# STM32H745.net
KiCad netlist of a schematic drawn in Altium Designer
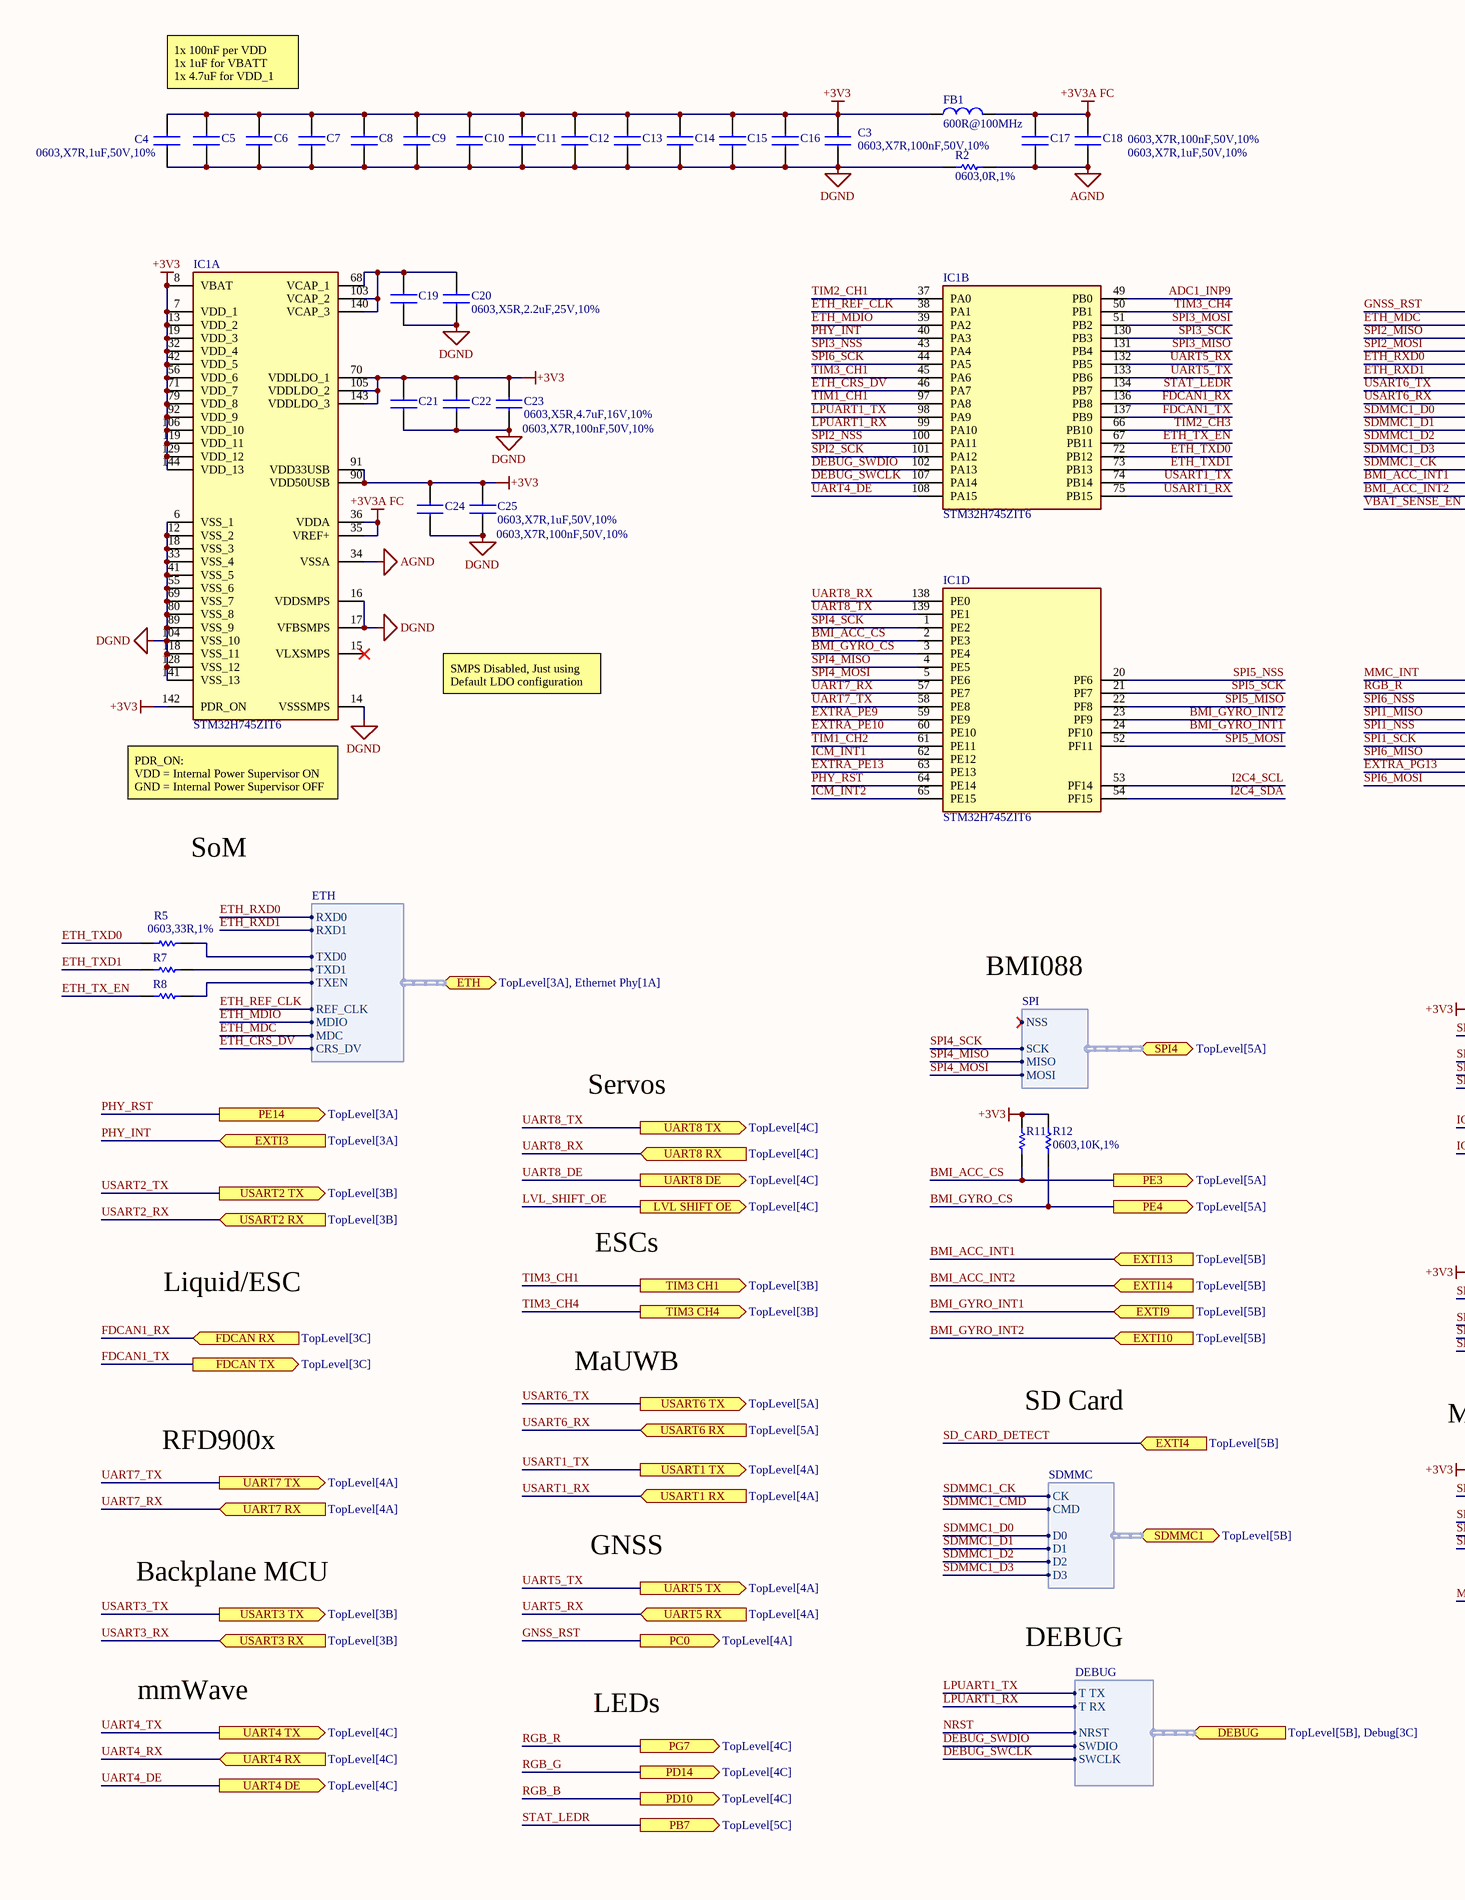
[diagram p0: STM32H745.SchDoc, left]
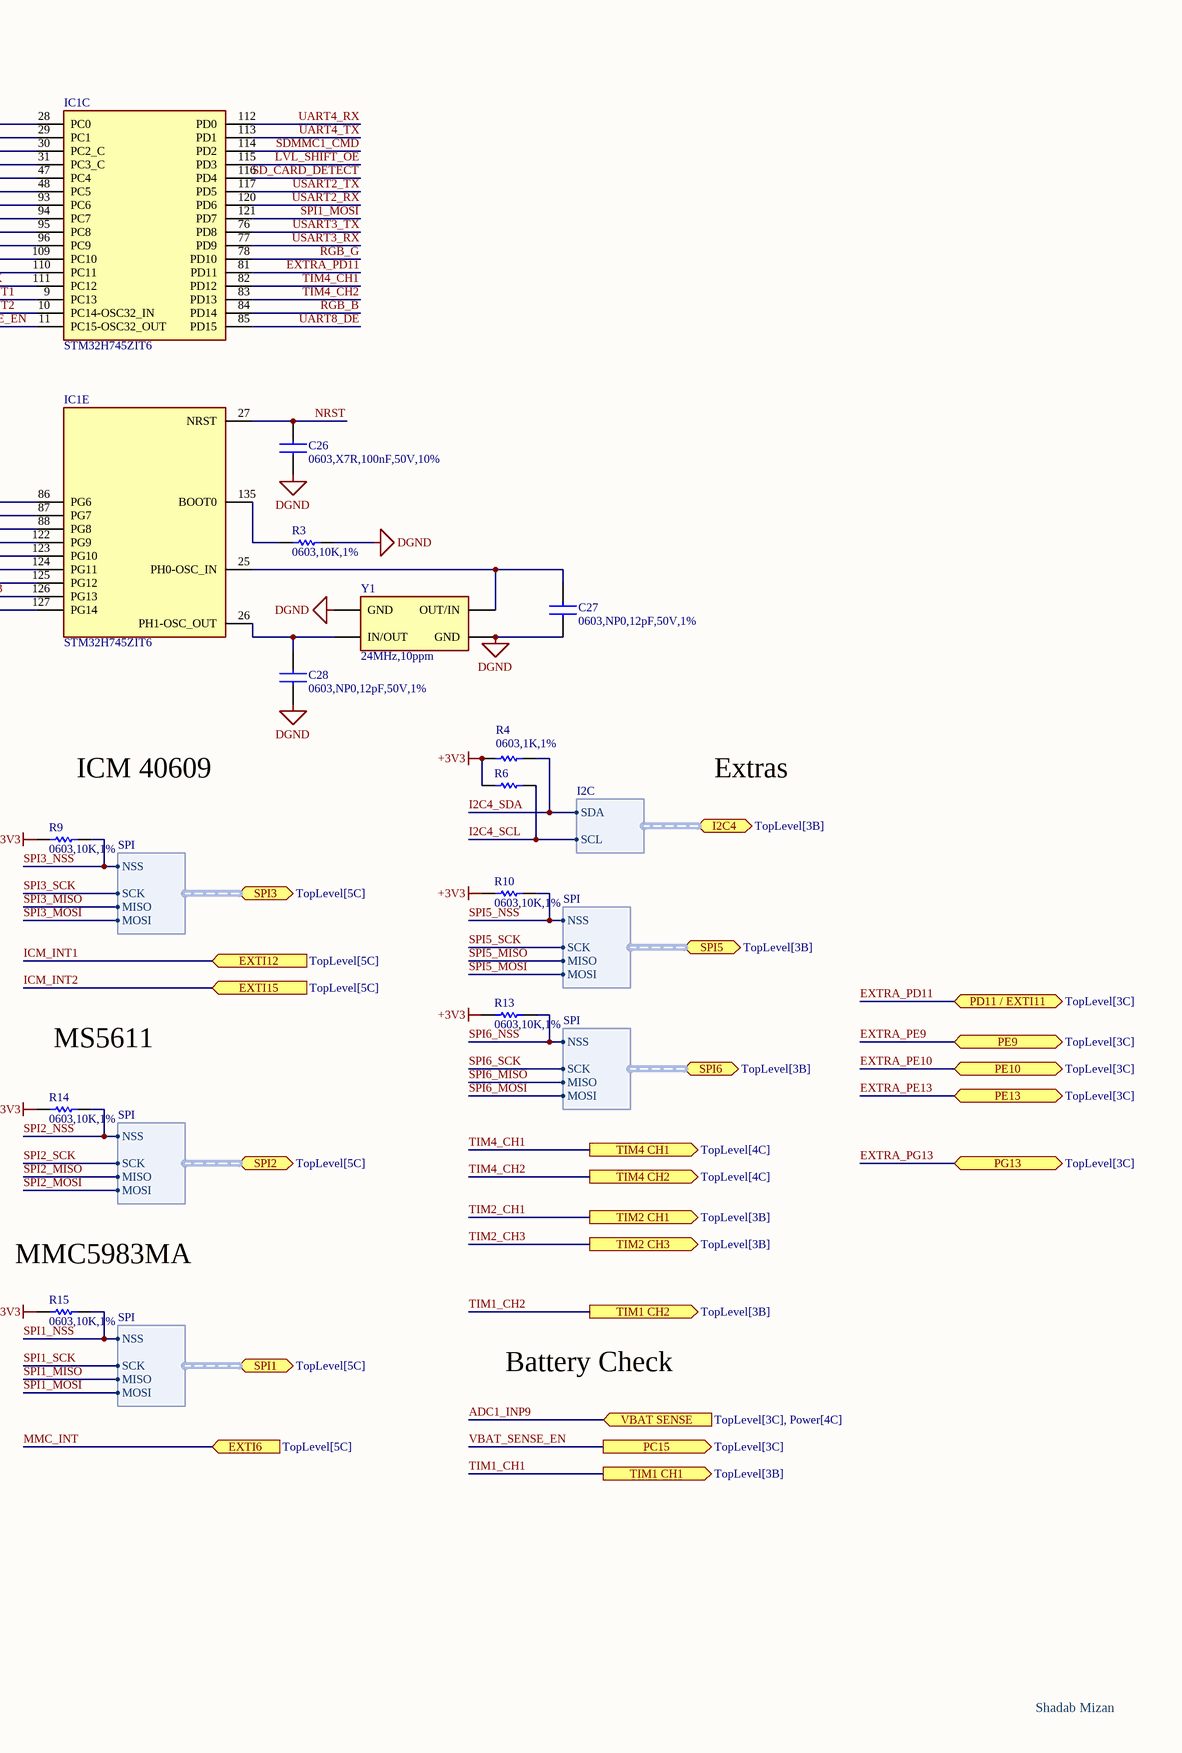
[diagram p1: STM32H745.SchDoc, right]

(export (version "E")
  (design (tool "Eeschema 10.0.6"))
  (components
    (comp (ref "C3")
      (value "0603,X7R,100nF,50V,10%")
      (footprint "CAPC1608X90N")
      (description "50V 100nF X7R ±10% 0603 Multilayer Ceramic Capacitors MLCC - SMD/SMT ROHS")
      (fields (field (name "LCSC PART #") "C14663") (field (name "MANU PART #") "CC0603KRX7R9BB104"))
      (libsource (lib "flight-controller") (part "CC0603KRX7R9BB104"))
    )
    (comp (ref "C4")
      (value "0603,X7R,1uF,50V,10%")
      (footprint "CAPC1608X90N")
      (description "50V 1uF X7R ±10% 0603 Multilayer Ceramic Capacitors MLCC - SMD/SMT ROHS")
      (fields (field (name "LCSC PART #") "C15849") (field (name "MANU PART #") "CL10A105KB8NNNC"))
      (libsource (lib "flight-controller") (part "CL10A105KB8NNNC"))
    )
    (comp (ref "C5")
      (value "0603,X7R,100nF,50V,10%")
      (footprint "CAPC1608X90N")
      (description "50V 100nF X7R ±10% 0603 Multilayer Ceramic Capacitors MLCC - SMD/SMT ROHS")
      (fields (field (name "LCSC PART #") "C14663") (field (name "MANU PART #") "CC0603KRX7R9BB104"))
      (libsource (lib "flight-controller") (part "CC0603KRX7R9BB104"))
    )
    (comp (ref "C6")
      (value "0603,X7R,100nF,50V,10%")
      (footprint "CAPC1608X90N")
      (description "50V 100nF X7R ±10% 0603 Multilayer Ceramic Capacitors MLCC - SMD/SMT ROHS")
      (fields (field (name "LCSC PART #") "C14663") (field (name "MANU PART #") "CC0603KRX7R9BB104"))
      (libsource (lib "flight-controller") (part "CC0603KRX7R9BB104"))
    )
    (comp (ref "C7")
      (value "0603,X7R,100nF,50V,10%")
      (footprint "CAPC1608X90N")
      (description "50V 100nF X7R ±10% 0603 Multilayer Ceramic Capacitors MLCC - SMD/SMT ROHS")
      (fields (field (name "LCSC PART #") "C14663") (field (name "MANU PART #") "CC0603KRX7R9BB104"))
      (libsource (lib "flight-controller") (part "CC0603KRX7R9BB104"))
    )
    (comp (ref "C8")
      (value "0603,X7R,100nF,50V,10%")
      (footprint "CAPC1608X90N")
      (description "50V 100nF X7R ±10% 0603 Multilayer Ceramic Capacitors MLCC - SMD/SMT ROHS")
      (fields (field (name "LCSC PART #") "C14663") (field (name "MANU PART #") "CC0603KRX7R9BB104"))
      (libsource (lib "flight-controller") (part "CC0603KRX7R9BB104"))
    )
    (comp (ref "C9")
      (value "0603,X7R,100nF,50V,10%")
      (footprint "CAPC1608X90N")
      (description "50V 100nF X7R ±10% 0603 Multilayer Ceramic Capacitors MLCC - SMD/SMT ROHS")
      (fields (field (name "LCSC PART #") "C14663") (field (name "MANU PART #") "CC0603KRX7R9BB104"))
      (libsource (lib "flight-controller") (part "CC0603KRX7R9BB104"))
    )
    (comp (ref "C10")
      (value "0603,X7R,100nF,50V,10%")
      (footprint "CAPC1608X90N")
      (description "50V 100nF X7R ±10% 0603 Multilayer Ceramic Capacitors MLCC - SMD/SMT ROHS")
      (fields (field (name "LCSC PART #") "C14663") (field (name "MANU PART #") "CC0603KRX7R9BB104"))
      (libsource (lib "flight-controller") (part "CC0603KRX7R9BB104"))
    )
    (comp (ref "C11")
      (value "0603,X7R,100nF,50V,10%")
      (footprint "CAPC1608X90N")
      (description "50V 100nF X7R ±10% 0603 Multilayer Ceramic Capacitors MLCC - SMD/SMT ROHS")
      (fields (field (name "LCSC PART #") "C14663") (field (name "MANU PART #") "CC0603KRX7R9BB104"))
      (libsource (lib "flight-controller") (part "CC0603KRX7R9BB104"))
    )
    (comp (ref "C12")
      (value "0603,X7R,100nF,50V,10%")
      (footprint "CAPC1608X90N")
      (description "50V 100nF X7R ±10% 0603 Multilayer Ceramic Capacitors MLCC - SMD/SMT ROHS")
      (fields (field (name "LCSC PART #") "C14663") (field (name "MANU PART #") "CC0603KRX7R9BB104"))
      (libsource (lib "flight-controller") (part "CC0603KRX7R9BB104"))
    )
    (comp (ref "C13")
      (value "0603,X7R,100nF,50V,10%")
      (footprint "CAPC1608X90N")
      (description "50V 100nF X7R ±10% 0603 Multilayer Ceramic Capacitors MLCC - SMD/SMT ROHS")
      (fields (field (name "LCSC PART #") "C14663") (field (name "MANU PART #") "CC0603KRX7R9BB104"))
      (libsource (lib "flight-controller") (part "CC0603KRX7R9BB104"))
    )
    (comp (ref "C14")
      (value "0603,X7R,100nF,50V,10%")
      (footprint "CAPC1608X90N")
      (description "50V 100nF X7R ±10% 0603 Multilayer Ceramic Capacitors MLCC - SMD/SMT ROHS")
      (fields (field (name "LCSC PART #") "C14663") (field (name "MANU PART #") "CC0603KRX7R9BB104"))
      (libsource (lib "flight-controller") (part "CC0603KRX7R9BB104"))
    )
    (comp (ref "C15")
      (value "0603,X7R,100nF,50V,10%")
      (footprint "CAPC1608X90N")
      (description "50V 100nF X7R ±10% 0603 Multilayer Ceramic Capacitors MLCC - SMD/SMT ROHS")
      (fields (field (name "LCSC PART #") "C14663") (field (name "MANU PART #") "CC0603KRX7R9BB104"))
      (libsource (lib "flight-controller") (part "CC0603KRX7R9BB104"))
    )
    (comp (ref "C16")
      (value "0603,X7R,100nF,50V,10%")
      (footprint "CAPC1608X90N")
      (description "50V 100nF X7R ±10% 0603 Multilayer Ceramic Capacitors MLCC - SMD/SMT ROHS")
      (fields (field (name "LCSC PART #") "C14663") (field (name "MANU PART #") "CC0603KRX7R9BB104"))
      (libsource (lib "flight-controller") (part "CC0603KRX7R9BB104"))
    )
    (comp (ref "C17")
      (value "0603,X7R,100nF,50V,10%")
      (footprint "CAPC1608X90N")
      (description "50V 100nF X7R ±10% 0603 Multilayer Ceramic Capacitors MLCC - SMD/SMT ROHS")
      (fields (field (name "LCSC PART #") "C14663") (field (name "MANU PART #") "CC0603KRX7R9BB104"))
      (libsource (lib "flight-controller") (part "CC0603KRX7R9BB104"))
    )
    (comp (ref "C18")
      (value "0603,X7R,1uF,50V,10%")
      (footprint "CAPC1608X90N")
      (description "50V 1uF X7R ±10% 0603 Multilayer Ceramic Capacitors MLCC - SMD/SMT ROHS")
      (fields (field (name "LCSC PART #") "C15849") (field (name "MANU PART #") "CL10A105KB8NNNC"))
      (libsource (lib "flight-controller") (part "CL10A105KB8NNNC"))
    )
    (comp (ref "C19")
      (value "0603,X5R,2.2uF,25V,10%")
      (footprint "CAPC1608X90N")
      (description "2.2 µF ±10% 25V Ceramic Capacitor X5R 0603 (1608 Metric)")
      (fields (field (name "MANU PART #") "CL10A225KO8NNNC") (field (name "LCSC PART #") "C23630"))
      (libsource (lib "flight-controller") (part "CL10A225KO8NNNC"))
    )
    (comp (ref "C20")
      (value "0603,X5R,2.2uF,25V,10%")
      (footprint "CAPC1608X90N")
      (description "2.2 µF ±10% 25V Ceramic Capacitor X5R 0603 (1608 Metric)")
      (fields (field (name "MANU PART #") "CL10A225KO8NNNC") (field (name "LCSC PART #") "C23630"))
      (libsource (lib "flight-controller") (part "CL10A225KO8NNNC"))
    )
    (comp (ref "C21")
      (value "0603,X7R,100nF,50V,10%")
      (footprint "CAPC1608X90N")
      (description "50V 100nF X7R ±10% 0603 Multilayer Ceramic Capacitors MLCC - SMD/SMT ROHS")
      (fields (field (name "LCSC PART #") "C14663") (field (name "MANU PART #") "CC0603KRX7R9BB104"))
      (libsource (lib "flight-controller") (part "CC0603KRX7R9BB104"))
    )
    (comp (ref "C22")
      (value "0603,X7R,100nF,50V,10%")
      (footprint "CAPC1608X90N")
      (description "50V 100nF X7R ±10% 0603 Multilayer Ceramic Capacitors MLCC - SMD/SMT ROHS")
      (fields (field (name "LCSC PART #") "C14663") (field (name "MANU PART #") "CC0603KRX7R9BB104"))
      (libsource (lib "flight-controller") (part "CC0603KRX7R9BB104"))
    )
    (comp (ref "C23")
      (value "0603,X5R,4.7uF,16V,10%")
      (footprint "CAPC1608X90N")
      (description "16V 4.7uF X5R ±10% 0603 Multilayer Ceramic Capacitors MLCC - SMD/SMT ROHS")
      (fields (field (name "LCSC PART #") "C19666") (field (name "MANU PART #") "CL10A475KO8NNNC"))
      (libsource (lib "flight-controller") (part "CL10A475KO8NNNC"))
    )
    (comp (ref "C24")
      (value "0603,X7R,100nF,50V,10%")
      (footprint "CAPC1608X90N")
      (description "50V 100nF X7R ±10% 0603 Multilayer Ceramic Capacitors MLCC - SMD/SMT ROHS")
      (fields (field (name "LCSC PART #") "C14663") (field (name "MANU PART #") "CC0603KRX7R9BB104"))
      (libsource (lib "flight-controller") (part "CC0603KRX7R9BB104"))
    )
    (comp (ref "C25")
      (value "0603,X7R,1uF,50V,10%")
      (footprint "CAPC1608X90N")
      (description "50V 1uF X7R ±10% 0603 Multilayer Ceramic Capacitors MLCC - SMD/SMT ROHS")
      (fields (field (name "LCSC PART #") "C15849") (field (name "MANU PART #") "CL10A105KB8NNNC"))
      (libsource (lib "flight-controller") (part "CL10A105KB8NNNC"))
    )
    (comp (ref "C26")
      (value "0603,X7R,100nF,50V,10%")
      (footprint "CAPC1608X90N")
      (description "50V 100nF X7R ±10% 0603 Multilayer Ceramic Capacitors MLCC - SMD/SMT ROHS")
      (fields (field (name "LCSC PART #") "C14663") (field (name "MANU PART #") "CC0603KRX7R9BB104"))
      (libsource (lib "flight-controller") (part "CC0603KRX7R9BB104"))
    )
    (comp (ref "C27")
      (value "0603,NP0,12pF,50V,1%")
      (footprint "CAPC1608X90N")
      (description "12pF ±1% 50V Ceramic Capacitor NP0 0603")
      (fields (field (name "LCSC PART #") "C38523") (field (name "MANU PART #") "CL10C120JB8NNNC"))
      (libsource (lib "flight-controller") (part "CL10C120JB8NNNC"))
    )
    (comp (ref "C28")
      (value "0603,NP0,12pF,50V,1%")
      (footprint "CAPC1608X90N")
      (description "12pF ±1% 50V Ceramic Capacitor NP0 0603")
      (fields (field (name "LCSC PART #") "C38523") (field (name "MANU PART #") "CL10C120JB8NNNC"))
      (libsource (lib "flight-controller") (part "CL10C120JB8NNNC"))
    )
    (comp (ref "FB1")
      (value "600R@100MHz")
      (footprint "BLM18SP221SN1B")
      (description "380mΩ ±25% 600Ω@100MHz 0603 Ferrite Beads ROHS")
      (fields (field (name "LCSC PART #") "C19330") (field (name "MANU PART #") "BLM18AG601SN1D"))
      (libsource (lib "flight-controller") (part "BLM18AG601SN1D"))
    )
    (comp (ref "IC1")
      (value "STM32H745ZIT6")
      (footprint "QFP50P2200X2200X160-144N")
      (fields (field (name "LCSC PART #") "C730193"))
      (libsource (lib "flight-controller") (part "STM32H745ZIT6"))
    )
    (comp (ref "R2")
      (value "0603,0R,1%")
      (footprint "RESC1608X90N")
      (description "0Ω 100mW 75V Thick Film Resistor ±1% 0603 Chip Resistor - Surface Mount RoHS")
      (fields (field (name "LCSC PART #") "C21189") (field (name "MANU PART #") "0603WAF0000T5E"))
      (libsource (lib "flight-controller") (part "0603WAF0000T5E"))
    )
    (comp (ref "R3")
      (value "0603,10K,1%")
      (footprint "RESC1608X90N")
      (description "100mW Thick Film Resistor 75V ±100ppm/℃ ±1% 10kΩ 0603 Chip Resistor - Surface Mount ROHS")
      (fields (field (name "LCSC PART #") "C25804") (field (name "MANU PART #") "0603WAF1002T5E"))
      (libsource (lib "flight-controller") (part "0603WAF1002T5E"))
    )
    (comp (ref "R4")
      (value "0603,1K,1%")
      (footprint "RESC1608X90N")
      (description "100mW 1kΩ 75V Thick Film Resistor ±100ppm/℃ ±1% 0603 Chip Resistor - Surface Mount RoHS")
      (fields (field (name "LCSC PART #") "C21190") (field (name "MANU PART #") "0603WAF1001T5E"))
      (libsource (lib "flight-controller") (part "0603WAF1001T5E"))
    )
    (comp (ref "R5")
      (value "0603,33R,1%")
      (footprint "RESC1608X90N")
      (description "100mW 33Ω 75V Thick Film Resistor ±100ppm/℃ ±1% 0603 Chip Resistor - Surface Mount RoHS")
      (fields (field (name "LCSC PART #") "C23140") (field (name "MANU PART #") "0603WAF330JT5E"))
      (libsource (lib "flight-controller") (part "0603WAF330JT5E"))
    )
    (comp (ref "R6")
      (value "0603,1K,1%")
      (footprint "RESC1608X90N")
      (description "100mW 1kΩ 75V Thick Film Resistor ±100ppm/℃ ±1% 0603 Chip Resistor - Surface Mount RoHS")
      (fields (field (name "LCSC PART #") "C21190") (field (name "MANU PART #") "0603WAF1001T5E"))
      (libsource (lib "flight-controller") (part "0603WAF1001T5E"))
    )
    (comp (ref "R7")
      (value "0603,33R,1%")
      (footprint "RESC1608X90N")
      (description "100mW 33Ω 75V Thick Film Resistor ±100ppm/℃ ±1% 0603 Chip Resistor - Surface Mount RoHS")
      (fields (field (name "LCSC PART #") "C23140") (field (name "MANU PART #") "0603WAF330JT5E"))
      (libsource (lib "flight-controller") (part "0603WAF330JT5E"))
    )
    (comp (ref "R8")
      (value "0603,33R,1%")
      (footprint "RESC1608X90N")
      (description "100mW 33Ω 75V Thick Film Resistor ±100ppm/℃ ±1% 0603 Chip Resistor - Surface Mount RoHS")
      (fields (field (name "LCSC PART #") "C23140") (field (name "MANU PART #") "0603WAF330JT5E"))
      (libsource (lib "flight-controller") (part "0603WAF330JT5E"))
    )
    (comp (ref "R9")
      (value "0603,10K,1%")
      (footprint "RESC1608X90N")
      (description "100mW Thick Film Resistor 75V ±100ppm/℃ ±1% 10kΩ 0603 Chip Resistor - Surface Mount ROHS")
      (fields (field (name "LCSC PART #") "C25804") (field (name "MANU PART #") "0603WAF1002T5E"))
      (libsource (lib "flight-controller") (part "0603WAF1002T5E"))
    )
    (comp (ref "R10")
      (value "0603,10K,1%")
      (footprint "RESC1608X90N")
      (description "100mW Thick Film Resistor 75V ±100ppm/℃ ±1% 10kΩ 0603 Chip Resistor - Surface Mount ROHS")
      (fields (field (name "LCSC PART #") "C25804") (field (name "MANU PART #") "0603WAF1002T5E"))
      (libsource (lib "flight-controller") (part "0603WAF1002T5E"))
    )
    (comp (ref "R11")
      (value "0603,10K,1%")
      (footprint "RESC1608X90N")
      (description "100mW Thick Film Resistor 75V ±100ppm/℃ ±1% 10kΩ 0603 Chip Resistor - Surface Mount ROHS")
      (fields (field (name "LCSC PART #") "C25804") (field (name "MANU PART #") "0603WAF1002T5E"))
      (libsource (lib "flight-controller") (part "0603WAF1002T5E"))
    )
    (comp (ref "R12")
      (value "0603,10K,1%")
      (footprint "RESC1608X90N")
      (description "100mW Thick Film Resistor 75V ±100ppm/℃ ±1% 10kΩ 0603 Chip Resistor - Surface Mount ROHS")
      (fields (field (name "LCSC PART #") "C25804") (field (name "MANU PART #") "0603WAF1002T5E"))
      (libsource (lib "flight-controller") (part "0603WAF1002T5E"))
    )
    (comp (ref "R13")
      (value "0603,10K,1%")
      (footprint "RESC1608X90N")
      (description "100mW Thick Film Resistor 75V ±100ppm/℃ ±1% 10kΩ 0603 Chip Resistor - Surface Mount ROHS")
      (fields (field (name "LCSC PART #") "C25804") (field (name "MANU PART #") "0603WAF1002T5E"))
      (libsource (lib "flight-controller") (part "0603WAF1002T5E"))
    )
    (comp (ref "R14")
      (value "0603,10K,1%")
      (footprint "RESC1608X90N")
      (description "100mW Thick Film Resistor 75V ±100ppm/℃ ±1% 10kΩ 0603 Chip Resistor - Surface Mount ROHS")
      (fields (field (name "LCSC PART #") "C25804") (field (name "MANU PART #") "0603WAF1002T5E"))
      (libsource (lib "flight-controller") (part "0603WAF1002T5E"))
    )
    (comp (ref "R15")
      (value "0603,10K,1%")
      (footprint "RESC1608X90N")
      (description "100mW Thick Film Resistor 75V ±100ppm/℃ ±1% 10kΩ 0603 Chip Resistor - Surface Mount ROHS")
      (fields (field (name "LCSC PART #") "C25804") (field (name "MANU PART #") "0603WAF1002T5E"))
      (libsource (lib "flight-controller") (part "0603WAF1002T5E"))
    )
    (comp (ref "Y1")
      (value "24MHz,10ppm")
      (footprint "CRYSTAL-SMD_4P-L3.2-W2.5-BL")
      (description "Crystal 24MHz ±10ppm 12pF 50Ω SMD3225-4P")
      (fields (field (name "MANU PART #") "XC32M4-24.000-F12NJDTL") (field (name "LCSC PART #") "C5122304"))
      (libsource (lib "flight-controller") (part "XC32M4-24.000-F12NJDTL"))
    )
  )
  (nets
    (net (code "6") (name "+3V3") (class "Default")
      (node (ref "C10") (pin "2") (pinfunction "2_2") (pintype "passive"))
      (node (ref "C11") (pin "2") (pinfunction "2_2") (pintype "passive"))
      (node (ref "C12") (pin "2") (pinfunction "2_2") (pintype "passive"))
      (node (ref "C13") (pin "2") (pinfunction "2_2") (pintype "passive"))
      (node (ref "C14") (pin "2") (pinfunction "2_2") (pintype "passive"))
      (node (ref "C15") (pin "2") (pinfunction "2_2") (pintype "passive"))
      (node (ref "C16") (pin "2") (pinfunction "2_2") (pintype "passive"))
      (node (ref "C21") (pin "2") (pinfunction "2_2") (pintype "passive"))
      (node (ref "C22") (pin "2") (pinfunction "2_2") (pintype "passive"))
      (node (ref "C23") (pin "2") (pinfunction "2_2") (pintype "passive"))
      (node (ref "C24") (pin "2") (pinfunction "2_2") (pintype "passive"))
      (node (ref "C25") (pin "2") (pinfunction "2_2") (pintype "passive"))
      (node (ref "C3") (pin "2") (pinfunction "2_2") (pintype "passive"))
      (node (ref "C4") (pin "2") (pinfunction "2_2") (pintype "passive"))
      (node (ref "C5") (pin "2") (pinfunction "2_2") (pintype "passive"))
      (node (ref "C6") (pin "2") (pinfunction "2_2") (pintype "passive"))
      (node (ref "C7") (pin "2") (pinfunction "2_2") (pintype "passive"))
      (node (ref "C8") (pin "2") (pinfunction "2_2") (pintype "passive"))
      (node (ref "C9") (pin "2") (pinfunction "2_2") (pintype "passive"))
      (node (ref "FB1") (pin "1") (pinfunction "1_1") (pintype "passive"))
      (node (ref "IC1") (pin "105") (pinfunction "VDDLDO_2_105") (pintype "passive"))
      (node (ref "IC1") (pin "106") (pinfunction "VDD_10_106") (pintype "passive"))
      (node (ref "IC1") (pin "119") (pinfunction "VDD_11_119") (pintype "passive"))
      (node (ref "IC1") (pin "129") (pinfunction "VDD_12_129") (pintype "passive"))
      (node (ref "IC1") (pin "13") (pinfunction "VDD_2_13") (pintype "passive"))
      (node (ref "IC1") (pin "142") (pinfunction "PDR_ON_142") (pintype "passive"))
      (node (ref "IC1") (pin "143") (pinfunction "VDDLDO_3_143") (pintype "passive"))
      (node (ref "IC1") (pin "144") (pinfunction "VDD_13_144") (pintype "passive"))
      (node (ref "IC1") (pin "19") (pinfunction "VDD_3_19") (pintype "passive"))
      (node (ref "IC1") (pin "32") (pinfunction "VDD_4_32") (pintype "passive"))
      (node (ref "IC1") (pin "42") (pinfunction "VDD_5_42") (pintype "passive"))
      (node (ref "IC1") (pin "56") (pinfunction "VDD_6_56") (pintype "passive"))
      (node (ref "IC1") (pin "7") (pinfunction "VDD_1_7") (pintype "passive"))
      (node (ref "IC1") (pin "70") (pinfunction "VDDLDO_1_70") (pintype "passive"))
      (node (ref "IC1") (pin "71") (pinfunction "VDD_7_71") (pintype "passive"))
      (node (ref "IC1") (pin "79") (pinfunction "VDD_8_79") (pintype "passive"))
      (node (ref "IC1") (pin "8") (pinfunction "VBAT_8") (pintype "passive"))
      (node (ref "IC1") (pin "90") (pinfunction "VDD50USB_90") (pintype "passive"))
      (node (ref "IC1") (pin "91") (pinfunction "VDD33USB_91") (pintype "passive"))
      (node (ref "IC1") (pin "92") (pinfunction "VDD_9_92") (pintype "passive"))
      (node (ref "R10") (pin "1") (pinfunction "1_1") (pintype "passive"))
      (node (ref "R11") (pin "2") (pinfunction "2_2") (pintype "passive"))
      (node (ref "R12") (pin "2") (pinfunction "2_2") (pintype "passive"))
      (node (ref "R13") (pin "1") (pinfunction "1_1") (pintype "passive"))
      (node (ref "R14") (pin "1") (pinfunction "1_1") (pintype "passive"))
      (node (ref "R15") (pin "1") (pinfunction "1_1") (pintype "passive"))
      (node (ref "R4") (pin "1") (pinfunction "1_1") (pintype "passive"))
      (node (ref "R6") (pin "1") (pinfunction "1_1") (pintype "passive"))
      (node (ref "R9") (pin "1") (pinfunction "1_1") (pintype "passive"))
    )
    (net (code "7") (name "+3V3A FC") (class "Default")
      (node (ref "C17") (pin "2") (pinfunction "2_2") (pintype "passive"))
      (node (ref "C18") (pin "2") (pinfunction "2_2") (pintype "passive"))
      (node (ref "FB1") (pin "2") (pinfunction "2_2") (pintype "passive"))
      (node (ref "IC1") (pin "35") (pinfunction "VREF+_35") (pintype "passive"))
      (node (ref "IC1") (pin "36") (pinfunction "VDDA_36") (pintype "passive"))
    )
    (net (code "8") (name "/ADC1_INP9") (class "Default")
      (node (ref "IC1") (pin "49") (pinfunction "PB0_49") (pintype "passive"))
    )
    (net (code "9") (name "/BMI_ACC_CS") (class "Default")
      (node (ref "IC1") (pin "2") (pinfunction "PE3_2") (pintype "passive"))
      (node (ref "R11") (pin "1") (pinfunction "1_1") (pintype "passive"))
    )
    (net (code "10") (name "/BMI_ACC_INT1") (class "Default")
      (node (ref "IC1") (pin "9") (pinfunction "PC13_9") (pintype "passive"))
    )
    (net (code "11") (name "/BMI_ACC_INT2") (class "Default")
      (node (ref "IC1") (pin "10") (pinfunction "PC14-OSC32_IN_10") (pintype "passive"))
    )
    (net (code "12") (name "/BMI_GYRO_CS") (class "Default")
      (node (ref "IC1") (pin "3") (pinfunction "PE4_3") (pintype "passive"))
      (node (ref "R12") (pin "1") (pinfunction "1_1") (pintype "passive"))
    )
    (net (code "13") (name "/BMI_GYRO_INT1") (class "Default")
      (node (ref "IC1") (pin "24") (pinfunction "PF10_24") (pintype "passive"))
    )
    (net (code "14") (name "/BMI_GYRO_INT2") (class "Default")
      (node (ref "IC1") (pin "23") (pinfunction "PF9_23") (pintype "passive"))
    )
    (net (code "15") (name "/DEBUG_SWCLK") (class "Default")
      (node (ref "IC1") (pin "107") (pinfunction "PA14_107") (pintype "passive"))
    )
    (net (code "16") (name "/DEBUG_SWDIO") (class "Default")
      (node (ref "IC1") (pin "102") (pinfunction "PA13_102") (pintype "passive"))
    )
    (net (code "17") (name "/ETH_CRS_DV") (class "Default")
      (node (ref "IC1") (pin "46") (pinfunction "PA7_46") (pintype "passive"))
    )
    (net (code "18") (name "/ETH_MDC") (class "Default")
      (node (ref "IC1") (pin "29") (pinfunction "PC1_29") (pintype "passive"))
    )
    (net (code "19") (name "/ETH_MDIO") (class "Default")
      (node (ref "IC1") (pin "39") (pinfunction "PA2_39") (pintype "passive"))
    )
    (net (code "20") (name "/ETH_REF_CLK") (class "Default")
      (node (ref "IC1") (pin "38") (pinfunction "PA1_38") (pintype "passive"))
    )
    (net (code "21") (name "/ETH_RXD0") (class "Default")
      (node (ref "IC1") (pin "47") (pinfunction "PC4_47") (pintype "passive"))
    )
    (net (code "22") (name "/ETH_RXD1") (class "Default")
      (node (ref "IC1") (pin "48") (pinfunction "PC5_48") (pintype "passive"))
    )
    (net (code "23") (name "/ETH_TXD0") (class "Default")
      (node (ref "IC1") (pin "72") (pinfunction "PB12_72") (pintype "passive"))
      (node (ref "R5") (pin "1") (pinfunction "1_1") (pintype "passive"))
    )
    (net (code "24") (name "/ETH_TXD1") (class "Default")
      (node (ref "IC1") (pin "73") (pinfunction "PB13_73") (pintype "passive"))
      (node (ref "R7") (pin "1") (pinfunction "1_1") (pintype "passive"))
    )
    (net (code "25") (name "/ETH_TX_EN") (class "Default")
      (node (ref "IC1") (pin "67") (pinfunction "PB11_67") (pintype "passive"))
      (node (ref "R8") (pin "1") (pinfunction "1_1") (pintype "passive"))
    )
    (net (code "26") (name "/EXTRA_PD11") (class "Default")
      (node (ref "IC1") (pin "81") (pinfunction "PD11_81") (pintype "passive"))
    )
    (net (code "27") (name "/EXTRA_PE9") (class "Default")
      (node (ref "IC1") (pin "59") (pinfunction "PE9_59") (pintype "passive"))
    )
    (net (code "28") (name "/EXTRA_PE10") (class "Default")
      (node (ref "IC1") (pin "60") (pinfunction "PE10_60") (pintype "passive"))
    )
    (net (code "29") (name "/EXTRA_PE13") (class "Default")
      (node (ref "IC1") (pin "63") (pinfunction "PE13_63") (pintype "passive"))
    )
    (net (code "30") (name "/EXTRA_PG13") (class "Default")
      (node (ref "IC1") (pin "126") (pinfunction "PG13_126") (pintype "passive"))
    )
    (net (code "31") (name "/FDCAN1_RX") (class "Default")
      (node (ref "IC1") (pin "136") (pinfunction "PB8_136") (pintype "passive"))
    )
    (net (code "32") (name "/FDCAN1_TX") (class "Default")
      (node (ref "IC1") (pin "137") (pinfunction "PB9_137") (pintype "passive"))
    )
    (net (code "33") (name "/GNSS_RST") (class "Default")
      (node (ref "IC1") (pin "28") (pinfunction "PC0_28") (pintype "passive"))
    )
    (net (code "34") (name "/I2C4_SCL") (class "Default")
      (node (ref "IC1") (pin "53") (pinfunction "PF14_53") (pintype "passive"))
      (node (ref "R6") (pin "2") (pinfunction "2_2") (pintype "passive"))
    )
    (net (code "35") (name "/I2C4_SDA") (class "Default")
      (node (ref "IC1") (pin "54") (pinfunction "PF15_54") (pintype "passive"))
      (node (ref "R4") (pin "2") (pinfunction "2_2") (pintype "passive"))
    )
    (net (code "36") (name "/ICM_INT1") (class "Default")
      (node (ref "IC1") (pin "62") (pinfunction "PE12_62") (pintype "passive"))
    )
    (net (code "37") (name "/ICM_INT2") (class "Default")
      (node (ref "IC1") (pin "65") (pinfunction "PE15_65") (pintype "passive"))
    )
    (net (code "38") (name "/LPUART1_RX") (class "Default")
      (node (ref "IC1") (pin "99") (pinfunction "PA10_99") (pintype "passive"))
    )
    (net (code "39") (name "/LPUART1_TX") (class "Default")
      (node (ref "IC1") (pin "98") (pinfunction "PA9_98") (pintype "passive"))
    )
    (net (code "40") (name "/LVL_SHIFT_OE") (class "Default")
      (node (ref "IC1") (pin "115") (pinfunction "PD3_115") (pintype "passive"))
    )
    (net (code "41") (name "/MMC_INT") (class "Default")
      (node (ref "IC1") (pin "86") (pinfunction "PG6_86") (pintype "passive"))
    )
    (net (code "42") (name "/NRST") (class "Default")
      (node (ref "C26") (pin "2") (pinfunction "2_2") (pintype "passive"))
      (node (ref "IC1") (pin "27") (pinfunction "NRST_27") (pintype "passive"))
    )
    (net (code "43") (name "/PHY_INT") (class "Default")
      (node (ref "IC1") (pin "40") (pinfunction "PA3_40") (pintype "passive"))
    )
    (net (code "44") (name "/PHY_RST") (class "Default")
      (node (ref "IC1") (pin "64") (pinfunction "PE14_64") (pintype "passive"))
    )
    (net (code "45") (name "/RGB_B") (class "Default")
      (node (ref "IC1") (pin "84") (pinfunction "PD14_84") (pintype "passive"))
    )
    (net (code "46") (name "/RGB_G") (class "Default")
      (node (ref "IC1") (pin "78") (pinfunction "PD10_78") (pintype "passive"))
    )
    (net (code "47") (name "/RGB_R") (class "Default")
      (node (ref "IC1") (pin "87") (pinfunction "PG7_87") (pintype "passive"))
    )
    (net (code "48") (name "/SDMMC1_CK") (class "Default")
      (node (ref "IC1") (pin "111") (pinfunction "PC12_111") (pintype "passive"))
    )
    (net (code "49") (name "/SDMMC1_CMD") (class "Default")
      (node (ref "IC1") (pin "114") (pinfunction "PD2_114") (pintype "passive"))
    )
    (net (code "50") (name "/SDMMC1_D0") (class "Default")
      (node (ref "IC1") (pin "95") (pinfunction "PC8_95") (pintype "passive"))
    )
    (net (code "51") (name "/SDMMC1_D1") (class "Default")
      (node (ref "IC1") (pin "96") (pinfunction "PC9_96") (pintype "passive"))
    )
    (net (code "52") (name "/SDMMC1_D2") (class "Default")
      (node (ref "IC1") (pin "109") (pinfunction "PC10_109") (pintype "passive"))
    )
    (net (code "53") (name "/SDMMC1_D3") (class "Default")
      (node (ref "IC1") (pin "110") (pinfunction "PC11_110") (pintype "passive"))
    )
    (net (code "54") (name "/SD_CARD_DETECT") (class "Default")
      (node (ref "IC1") (pin "116") (pinfunction "PD4_116") (pintype "passive"))
    )
    (net (code "55") (name "/SPI1_MISO") (class "Default")
      (node (ref "IC1") (pin "122") (pinfunction "PG9_122") (pintype "passive"))
    )
    (net (code "56") (name "/SPI1_MOSI") (class "Default")
      (node (ref "IC1") (pin "121") (pinfunction "PD7_121") (pintype "passive"))
    )
    (net (code "57") (name "/SPI1_NSS") (class "Default")
      (node (ref "IC1") (pin "123") (pinfunction "PG10_123") (pintype "passive"))
      (node (ref "R15") (pin "2") (pinfunction "2_2") (pintype "passive"))
    )
    (net (code "58") (name "/SPI1_SCK") (class "Default")
      (node (ref "IC1") (pin "124") (pinfunction "PG11_124") (pintype "passive"))
    )
    (net (code "59") (name "/SPI2_MISO") (class "Default")
      (node (ref "IC1") (pin "30") (pinfunction "PC2_C_30") (pintype "passive"))
    )
    (net (code "60") (name "/SPI2_MOSI") (class "Default")
      (node (ref "IC1") (pin "31") (pinfunction "PC3_C_31") (pintype "passive"))
    )
    (net (code "61") (name "/SPI2_NSS") (class "Default")
      (node (ref "IC1") (pin "100") (pinfunction "PA11_100") (pintype "passive"))
      (node (ref "R14") (pin "2") (pinfunction "2_2") (pintype "passive"))
    )
    (net (code "62") (name "/SPI2_SCK") (class "Default")
      (node (ref "IC1") (pin "101") (pinfunction "PA12_101") (pintype "passive"))
    )
    (net (code "63") (name "/SPI3_MISO") (class "Default")
      (node (ref "IC1") (pin "131") (pinfunction "PB4_131") (pintype "passive"))
    )
    (net (code "64") (name "/SPI3_MOSI") (class "Default")
      (node (ref "IC1") (pin "51") (pinfunction "PB2_51") (pintype "passive"))
    )
    (net (code "65") (name "/SPI3_NSS") (class "Default")
      (node (ref "IC1") (pin "43") (pinfunction "PA4_43") (pintype "passive"))
      (node (ref "R9") (pin "2") (pinfunction "2_2") (pintype "passive"))
    )
    (net (code "66") (name "/SPI3_SCK") (class "Default")
      (node (ref "IC1") (pin "130") (pinfunction "PB3_130") (pintype "passive"))
    )
    (net (code "67") (name "/SPI4_MISO") (class "Default")
      (node (ref "IC1") (pin "4") (pinfunction "PE5_4") (pintype "passive"))
    )
    (net (code "68") (name "/SPI4_MOSI") (class "Default")
      (node (ref "IC1") (pin "5") (pinfunction "PE6_5") (pintype "passive"))
    )
    (net (code "69") (name "/SPI4_SCK") (class "Default")
      (node (ref "IC1") (pin "1") (pinfunction "PE2_1") (pintype "passive"))
    )
    (net (code "70") (name "/SPI5_MISO") (class "Default")
      (node (ref "IC1") (pin "22") (pinfunction "PF8_22") (pintype "passive"))
    )
    (net (code "71") (name "/SPI5_MOSI") (class "Default")
      (node (ref "IC1") (pin "52") (pinfunction "PF11_52") (pintype "passive"))
    )
    (net (code "72") (name "/SPI5_NSS") (class "Default")
      (node (ref "IC1") (pin "20") (pinfunction "PF6_20") (pintype "passive"))
      (node (ref "R10") (pin "2") (pinfunction "2_2") (pintype "passive"))
    )
    (net (code "73") (name "/SPI5_SCK") (class "Default")
      (node (ref "IC1") (pin "21") (pinfunction "PF7_21") (pintype "passive"))
    )
    (net (code "74") (name "/SPI6_MISO") (class "Default")
      (node (ref "IC1") (pin "125") (pinfunction "PG12_125") (pintype "passive"))
    )
    (net (code "75") (name "/SPI6_MOSI") (class "Default")
      (node (ref "IC1") (pin "127") (pinfunction "PG14_127") (pintype "passive"))
    )
    (net (code "76") (name "/SPI6_NSS") (class "Default")
      (node (ref "IC1") (pin "88") (pinfunction "PG8_88") (pintype "passive"))
      (node (ref "R13") (pin "2") (pinfunction "2_2") (pintype "passive"))
    )
    (net (code "77") (name "/SPI6_SCK") (class "Default")
      (node (ref "IC1") (pin "44") (pinfunction "PA5_44") (pintype "passive"))
    )
    (net (code "78") (name "/STAT_LEDR") (class "Default")
      (node (ref "IC1") (pin "134") (pinfunction "PB7_134") (pintype "passive"))
    )
    (net (code "79") (name "/TIM1_CH1") (class "Default")
      (node (ref "IC1") (pin "97") (pinfunction "PA8_97") (pintype "passive"))
    )
    (net (code "80") (name "/TIM1_CH2") (class "Default")
      (node (ref "IC1") (pin "61") (pinfunction "PE11_61") (pintype "passive"))
    )
    (net (code "81") (name "/TIM2_CH1") (class "Default")
      (node (ref "IC1") (pin "37") (pinfunction "PA0_37") (pintype "passive"))
    )
    (net (code "82") (name "/TIM2_CH3") (class "Default")
      (node (ref "IC1") (pin "66") (pinfunction "PB10_66") (pintype "passive"))
    )
    (net (code "83") (name "/TIM3_CH1") (class "Default")
      (node (ref "IC1") (pin "45") (pinfunction "PA6_45") (pintype "passive"))
    )
    (net (code "84") (name "/TIM3_CH4") (class "Default")
      (node (ref "IC1") (pin "50") (pinfunction "PB1_50") (pintype "passive"))
    )
    (net (code "85") (name "/TIM4_CH1") (class "Default")
      (node (ref "IC1") (pin "82") (pinfunction "PD12_82") (pintype "passive"))
    )
    (net (code "86") (name "/TIM4_CH2") (class "Default")
      (node (ref "IC1") (pin "83") (pinfunction "PD13_83") (pintype "passive"))
    )
    (net (code "87") (name "/TXD0") (class "Default")
      (node (ref "R5") (pin "2") (pinfunction "2_2") (pintype "passive"))
    )
    (net (code "88") (name "/TXD1") (class "Default")
      (node (ref "R7") (pin "2") (pinfunction "2_2") (pintype "passive"))
    )
    (net (code "89") (name "/TXEN") (class "Default")
      (node (ref "R8") (pin "2") (pinfunction "2_2") (pintype "passive"))
    )
    (net (code "90") (name "/UART4_DE") (class "Default")
      (node (ref "IC1") (pin "108") (pinfunction "PA15_108") (pintype "passive"))
    )
    (net (code "91") (name "/UART4_RX") (class "Default")
      (node (ref "IC1") (pin "112") (pinfunction "PD0_112") (pintype "passive"))
    )
    (net (code "92") (name "/UART4_TX") (class "Default")
      (node (ref "IC1") (pin "113") (pinfunction "PD1_113") (pintype "passive"))
    )
    (net (code "93") (name "/UART5_RX") (class "Default")
      (node (ref "IC1") (pin "132") (pinfunction "PB5_132") (pintype "passive"))
    )
    (net (code "94") (name "/UART5_TX") (class "Default")
      (node (ref "IC1") (pin "133") (pinfunction "PB6_133") (pintype "passive"))
    )
    (net (code "95") (name "/UART7_RX") (class "Default")
      (node (ref "IC1") (pin "57") (pinfunction "PE7_57") (pintype "passive"))
    )
    (net (code "96") (name "/UART7_TX") (class "Default")
      (node (ref "IC1") (pin "58") (pinfunction "PE8_58") (pintype "passive"))
    )
    (net (code "97") (name "/UART8_DE") (class "Default")
      (node (ref "IC1") (pin "85") (pinfunction "PD15_85") (pintype "passive"))
    )
    (net (code "98") (name "/UART8_RX") (class "Default")
      (node (ref "IC1") (pin "138") (pinfunction "PE0_138") (pintype "passive"))
    )
    (net (code "99") (name "/UART8_TX") (class "Default")
      (node (ref "IC1") (pin "139") (pinfunction "PE1_139") (pintype "passive"))
    )
    (net (code "100") (name "/USART1_RX") (class "Default")
      (node (ref "IC1") (pin "75") (pinfunction "PB15_75") (pintype "passive"))
    )
    (net (code "101") (name "/USART1_TX") (class "Default")
      (node (ref "IC1") (pin "74") (pinfunction "PB14_74") (pintype "passive"))
    )
    (net (code "102") (name "/USART2_RX") (class "Default")
      (node (ref "IC1") (pin "120") (pinfunction "PD6_120") (pintype "passive"))
    )
    (net (code "103") (name "/USART2_TX") (class "Default")
      (node (ref "IC1") (pin "117") (pinfunction "PD5_117") (pintype "passive"))
    )
    (net (code "104") (name "/USART3_RX") (class "Default")
      (node (ref "IC1") (pin "77") (pinfunction "PD9_77") (pintype "passive"))
    )
    (net (code "105") (name "/USART3_TX") (class "Default")
      (node (ref "IC1") (pin "76") (pinfunction "PD8_76") (pintype "passive"))
    )
    (net (code "106") (name "/USART6_RX") (class "Default")
      (node (ref "IC1") (pin "94") (pinfunction "PC7_94") (pintype "passive"))
    )
    (net (code "107") (name "/USART6_TX") (class "Default")
      (node (ref "IC1") (pin "93") (pinfunction "PC6_93") (pintype "passive"))
    )
    (net (code "108") (name "/VBAT_SENSE_EN") (class "Default")
      (node (ref "IC1") (pin "11") (pinfunction "PC15-OSC32_OUT_11") (pintype "passive"))
    )
    (net (code "114") (name "AGND") (class "Default")
      (node (ref "C17") (pin "1") (pinfunction "1_1") (pintype "passive"))
      (node (ref "C18") (pin "1") (pinfunction "1_1") (pintype "passive"))
      (node (ref "IC1") (pin "34") (pinfunction "VSSA_34") (pintype "passive"))
      (node (ref "R2") (pin "2") (pinfunction "2_2") (pintype "passive"))
    )
    (net (code "115") (name "DGND") (class "Default")
      (node (ref "C10") (pin "1") (pinfunction "1_1") (pintype "passive"))
      (node (ref "C11") (pin "1") (pinfunction "1_1") (pintype "passive"))
      (node (ref "C12") (pin "1") (pinfunction "1_1") (pintype "passive"))
      (node (ref "C13") (pin "1") (pinfunction "1_1") (pintype "passive"))
      (node (ref "C14") (pin "1") (pinfunction "1_1") (pintype "passive"))
      (node (ref "C15") (pin "1") (pinfunction "1_1") (pintype "passive"))
      (node (ref "C16") (pin "1") (pinfunction "1_1") (pintype "passive"))
      (node (ref "C19") (pin "1") (pinfunction "1_1") (pintype "passive"))
      (node (ref "C20") (pin "1") (pinfunction "1_1") (pintype "passive"))
      (node (ref "C21") (pin "1") (pinfunction "1_1") (pintype "passive"))
      (node (ref "C22") (pin "1") (pinfunction "1_1") (pintype "passive"))
      (node (ref "C23") (pin "1") (pinfunction "1_1") (pintype "passive"))
      (node (ref "C24") (pin "1") (pinfunction "1_1") (pintype "passive"))
      (node (ref "C25") (pin "1") (pinfunction "1_1") (pintype "passive"))
      (node (ref "C26") (pin "1") (pinfunction "1_1") (pintype "passive"))
      (node (ref "C27") (pin "1") (pinfunction "1_1") (pintype "passive"))
      (node (ref "C28") (pin "1") (pinfunction "1_1") (pintype "passive"))
      (node (ref "C3") (pin "1") (pinfunction "1_1") (pintype "passive"))
      (node (ref "C4") (pin "1") (pinfunction "1_1") (pintype "passive"))
      (node (ref "C5") (pin "1") (pinfunction "1_1") (pintype "passive"))
      (node (ref "C6") (pin "1") (pinfunction "1_1") (pintype "passive"))
      (node (ref "C7") (pin "1") (pinfunction "1_1") (pintype "passive"))
      (node (ref "C8") (pin "1") (pinfunction "1_1") (pintype "passive"))
      (node (ref "C9") (pin "1") (pinfunction "1_1") (pintype "passive"))
      (node (ref "IC1") (pin "104") (pinfunction "VSS_10_104") (pintype "passive"))
      (node (ref "IC1") (pin "118") (pinfunction "VSS_11_118") (pintype "passive"))
      (node (ref "IC1") (pin "12") (pinfunction "VSS_2_12") (pintype "passive"))
      (node (ref "IC1") (pin "128") (pinfunction "VSS_12_128") (pintype "passive"))
      (node (ref "IC1") (pin "14") (pinfunction "VSSSMPS_14") (pintype "passive"))
      (node (ref "IC1") (pin "141") (pinfunction "VSS_13_141") (pintype "passive"))
      (node (ref "IC1") (pin "16") (pinfunction "VDDSMPS_16") (pintype "passive"))
      (node (ref "IC1") (pin "17") (pinfunction "VFBSMPS_17") (pintype "passive"))
      (node (ref "IC1") (pin "18") (pinfunction "VSS_3_18") (pintype "passive"))
      (node (ref "IC1") (pin "33") (pinfunction "VSS_4_33") (pintype "passive"))
      (node (ref "IC1") (pin "41") (pinfunction "VSS_5_41") (pintype "passive"))
      (node (ref "IC1") (pin "55") (pinfunction "VSS_6_55") (pintype "passive"))
      (node (ref "IC1") (pin "6") (pinfunction "VSS_1_6") (pintype "passive"))
      (node (ref "IC1") (pin "69") (pinfunction "VSS_7_69") (pintype "passive"))
      (node (ref "IC1") (pin "80") (pinfunction "VSS_8_80") (pintype "passive"))
      (node (ref "IC1") (pin "89") (pinfunction "VSS_9_89") (pintype "passive"))
      (node (ref "R2") (pin "1") (pinfunction "1_1") (pintype "passive"))
      (node (ref "R3") (pin "2") (pinfunction "2_2") (pintype "passive"))
      (node (ref "Y1") (pin "2") (pinfunction "GND_2") (pintype "passive"))
      (node (ref "Y1") (pin "4") (pinfunction "GND_4") (pintype "passive"))
    )
    (net (code "116") (name "Net-(IC1A-VCAP_1)") (class "Default")
      (node (ref "C19") (pin "2") (pinfunction "2_2") (pintype "passive"))
      (node (ref "C20") (pin "2") (pinfunction "2_2") (pintype "passive"))
      (node (ref "IC1") (pin "103") (pinfunction "VCAP_2_103") (pintype "passive"))
      (node (ref "IC1") (pin "140") (pinfunction "VCAP_3_140") (pintype "passive"))
      (node (ref "IC1") (pin "68") (pinfunction "VCAP_1_68") (pintype "passive"))
    )
    (net (code "117") (name "Net-(IC1E-BOOT0)") (class "Default")
      (node (ref "IC1") (pin "135") (pinfunction "BOOT0_135") (pintype "passive"))
      (node (ref "R3") (pin "1") (pinfunction "1_1") (pintype "passive"))
    )
    (net (code "118") (name "Net-(IC1E-PH0-OSC_IN)") (class "Default")
      (node (ref "C27") (pin "2") (pinfunction "2_2") (pintype "passive"))
      (node (ref "IC1") (pin "25") (pinfunction "PH0-OSC_IN_25") (pintype "passive"))
      (node (ref "Y1") (pin "3") (pinfunction "OUT/IN_3") (pintype "passive"))
    )
    (net (code "119") (name "Net-(IC1E-PH1-OSC_OUT)") (class "Default")
      (node (ref "C28") (pin "2") (pinfunction "2_2") (pintype "passive"))
      (node (ref "IC1") (pin "26") (pinfunction "PH1-OSC_OUT_26") (pintype "passive"))
      (node (ref "Y1") (pin "1") (pinfunction "IN/OUT_1") (pintype "passive"))
    )
    (net (code "120") (name "unconnected-(IC1A-VLXSMPS-Pad15)") (class "Default")
      (node (ref "IC1") (pin "15") (pinfunction "VLXSMPS_15") (pintype "passive+no_connect"))
    )
  )
)
